# Wallboxsteuerung-WEMOS-ohne-shelly2.net
KiCad netlist of a schematic drawn in EAGLE
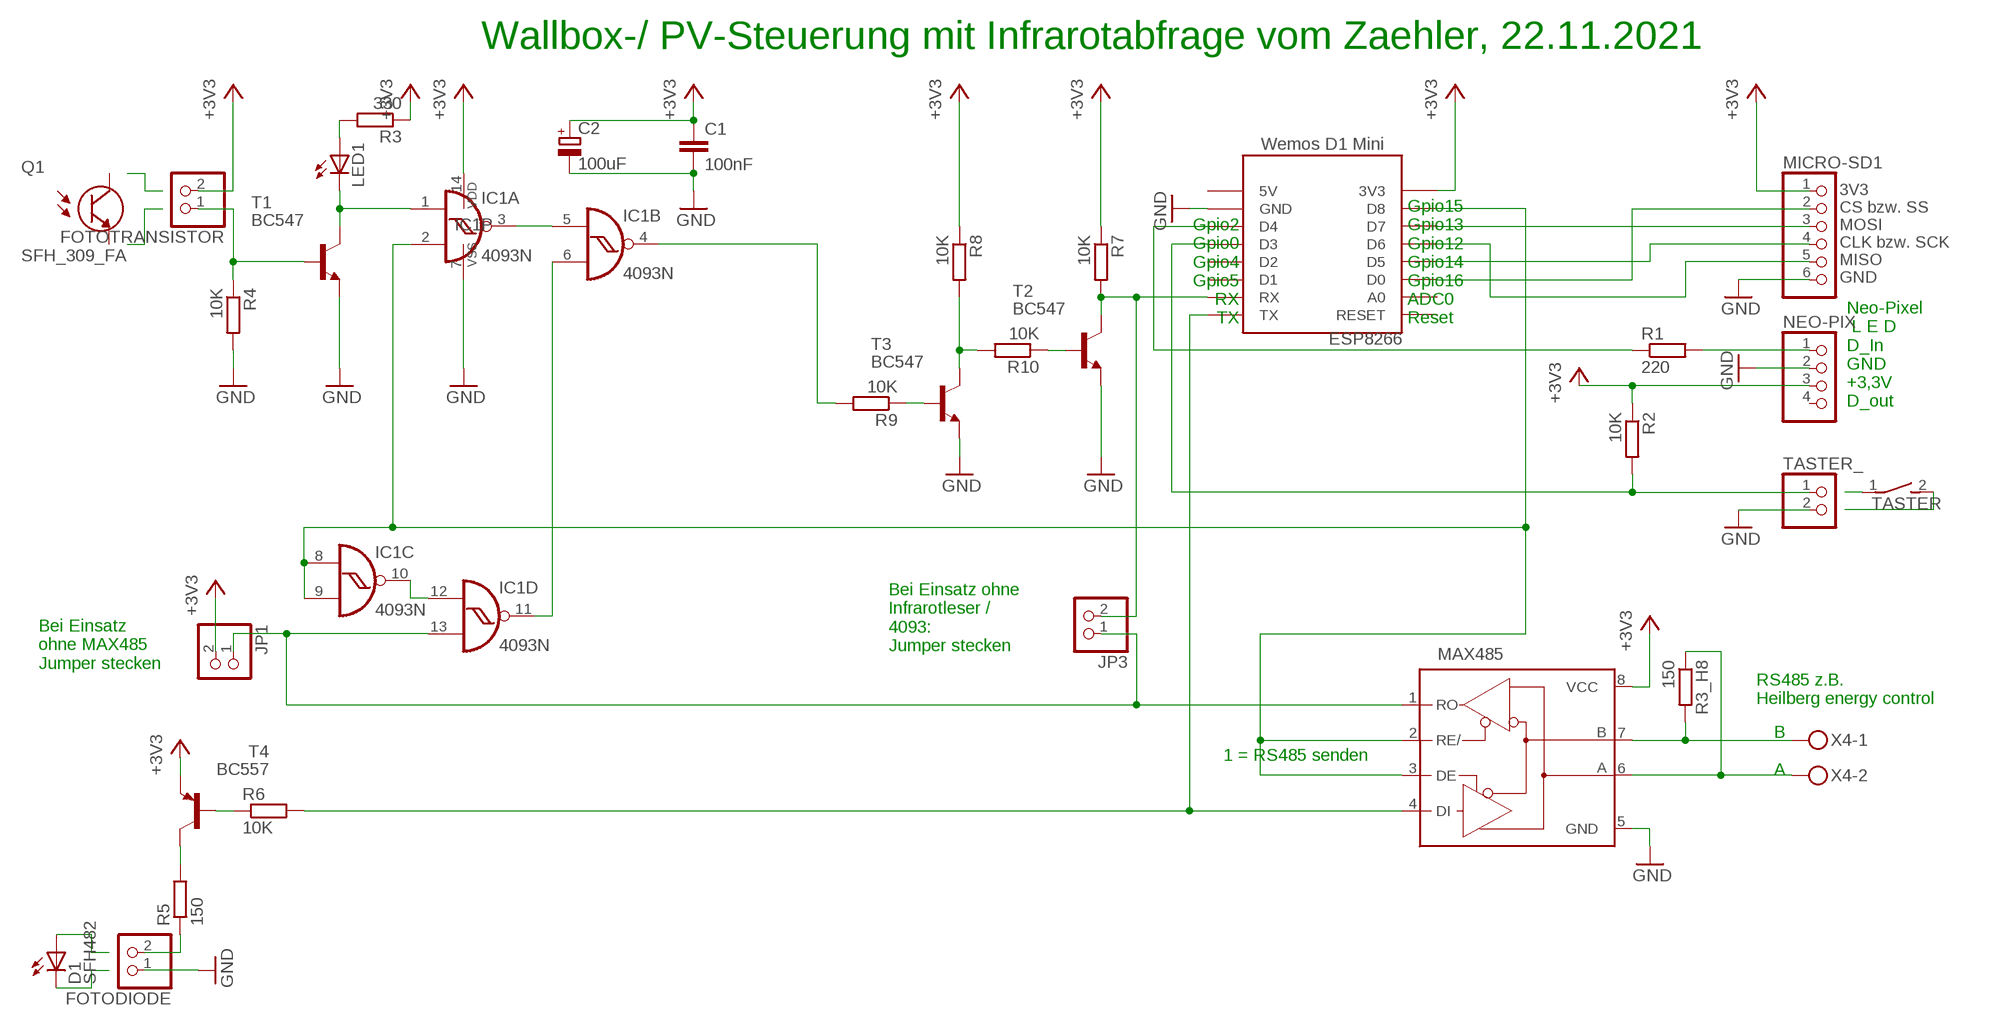
[diagram p0: schematic, sheet 1]

(export (version "E")
  (design (tool "Eeschema 10.0.6"))
  (components
    (comp (ref "C1")
      (value "100nF")
      (footprint "eagle-import:C050-045X075")
      (libsource (lib "eagle-import") (part "C-EU050-045X075"))
    )
    (comp (ref "C2")
      (value "100uF")
      (footprint "eagle-import:E5-6")
      (libsource (lib "eagle-import") (part "CPOL-EUE5-6"))
    )
    (comp (ref "D1")
      (value "SFH482")
      (footprint "eagle-import:SFH482")
      (libsource (lib "eagle-import") (part "SFH482"))
    )
    (comp (ref "ESP8266")
      (value "Wemos D1 Mini")
      (footprint "eagle-import:WEMOS-D1-MINI")
      (libsource (lib "eagle-import") (part "WEMOS-D1-MINI"))
    )
    (comp (ref "FOTODIODE")
      (value "PINHD-1X2")
      (footprint "eagle-import:1X02")
      (libsource (lib "eagle-import") (part "PINHD-1X2"))
    )
    (comp (ref "FOTOTRANSISTOR")
      (value "PINHD-1X2")
      (footprint "eagle-import:1X02")
      (libsource (lib "eagle-import") (part "PINHD-1X2"))
    )
    (comp (ref "IC1")
      (value "4093N")
      (footprint "eagle-import:DIL14")
      (libsource (lib "eagle-import") (part "4093N"))
    )
    (comp (ref "JP1")
      (value "PINHD-1X2")
      (footprint "eagle-import:1X02")
      (libsource (lib "eagle-import") (part "PINHD-1X2"))
    )
    (comp (ref "JP3")
      (value "PINHD-1X2")
      (footprint "eagle-import:1X02")
      (libsource (lib "eagle-import") (part "PINHD-1X2"))
    )
    (comp (ref "LED1")
      (value "LED5MM")
      (footprint "eagle-import:LED5MM")
      (libsource (lib "eagle-import") (part "LED5MM"))
    )
    (comp (ref "MAX485")
      (value "MAX3468CPA")
      (footprint "eagle-import:DIL08")
      (libsource (lib "eagle-import") (part "MAX34PA68C"))
    )
    (comp (ref "MICRO-SD1")
      (value "PINHD-1X6")
      (footprint "eagle-import:1X06")
      (libsource (lib "eagle-import") (part "PINHD-1X6"))
    )
    (comp (ref "NEO-PIX")
      (value "PINHD-1X4")
      (footprint "eagle-import:1X04")
      (libsource (lib "eagle-import") (part "PINHD-1X4"))
    )
    (comp (ref "Q1")
      (value "SFH_309_FA")
      (footprint "eagle-import:XDCR_SFH_309_FA")
      (fields (field (name "MANUFACTURER") "OSRAM"))
      (libsource (lib "eagle-import") (part "SFH_309_FA"))
    )
    (comp (ref "R1")
      (value "220")
      (footprint "eagle-import:0309V")
      (libsource (lib "eagle-import") (part "R-EU_0309/V"))
    )
    (comp (ref "R2")
      (value "10K")
      (footprint "eagle-import:0309V")
      (libsource (lib "eagle-import") (part "R-EU_0309/V"))
    )
    (comp (ref "R3")
      (value "330")
      (footprint "eagle-import:0309V")
      (libsource (lib "eagle-import") (part "R-EU_0309/V"))
    )
    (comp (ref "R3_H8")
      (value "150")
      (footprint "eagle-import:0309V")
      (libsource (lib "eagle-import") (part "R-EU_0309/V"))
    )
    (comp (ref "R4")
      (value "10K")
      (footprint "eagle-import:0309V")
      (libsource (lib "eagle-import") (part "R-EU_0309/V"))
    )
    (comp (ref "R5")
      (value "150")
      (footprint "eagle-import:0309V")
      (libsource (lib "eagle-import") (part "R-EU_0309/V"))
    )
    (comp (ref "R6")
      (value "10K")
      (footprint "eagle-import:0309V")
      (libsource (lib "eagle-import") (part "R-EU_0309/V"))
    )
    (comp (ref "R7")
      (value "10K")
      (footprint "eagle-import:0309V")
      (libsource (lib "eagle-import") (part "R-EU_0309/V"))
    )
    (comp (ref "R8")
      (value "10K")
      (footprint "eagle-import:0309V")
      (libsource (lib "eagle-import") (part "R-EU_0309/V"))
    )
    (comp (ref "R9")
      (value "10K")
      (footprint "eagle-import:0309V")
      (libsource (lib "eagle-import") (part "R-EU_0309/V"))
    )
    (comp (ref "R10")
      (value "10K")
      (footprint "eagle-import:0309V")
      (libsource (lib "eagle-import") (part "R-EU_0309/V"))
    )
    (comp (ref "T1")
      (value "BC547")
      (footprint "eagle-import:TO92")
      (libsource (lib "eagle-import") (part "BC547"))
    )
    (comp (ref "T2")
      (value "BC547")
      (footprint "eagle-import:TO92")
      (libsource (lib "eagle-import") (part "BC547"))
    )
    (comp (ref "T3")
      (value "BC547")
      (footprint "eagle-import:TO92")
      (libsource (lib "eagle-import") (part "BC547"))
    )
    (comp (ref "T4")
      (value "BC557")
      (footprint "eagle-import:TO92")
      (libsource (lib "eagle-import") (part "BC557"))
    )
    (comp (ref "TASTER")
      (value "DS01E")
      (footprint "eagle-import:DS-01")
      (libsource (lib "eagle-import") (part "DS01E"))
    )
    (comp (ref "TASTER_")
      (value "PINHD-1X2")
      (footprint "eagle-import:1X02")
      (libsource (lib "eagle-import") (part "PINHD-1X2"))
    )
    (comp (ref "X4")
      (value "MKDSN1,5/2-5,08")
      (footprint "eagle-import:MKDSN1,5_2-5,08")
      (libsource (lib "eagle-import") (part "MKDSN1,5/2-5,08"))
    )
  )
  (nets
    (net (code "1") (name "+3V3") (class "Default")
      (node (ref "C1") (pin "1") (pinfunction "1_1") (pintype "passive"))
      (node (ref "C2") (pin "+") (pinfunction "+_+") (pintype "passive"))
      (node (ref "ESP8266") (pin "3V3") (pinfunction "3V3_3V3") (pintype "bidirectional"))
      (node (ref "FOTOTRANSISTOR") (pin "2") (pinfunction "2_2") (pintype "passive"))
      (node (ref "IC1") (pin "14") (pinfunction "VDD_14") (pintype "power_in"))
      (node (ref "JP1") (pin "2") (pinfunction "2_2") (pintype "passive"))
      (node (ref "MAX485") (pin "8") (pinfunction "VCC_8") (pintype "power_in"))
      (node (ref "MICRO-SD1") (pin "1") (pinfunction "1_1") (pintype "passive"))
      (node (ref "NEO-PIX") (pin "3") (pinfunction "3_3") (pintype "passive"))
      (node (ref "R2") (pin "1") (pinfunction "1_1") (pintype "passive"))
      (node (ref "R3") (pin "1") (pinfunction "1_1") (pintype "passive"))
      (node (ref "R7") (pin "1") (pinfunction "1_1") (pintype "passive"))
      (node (ref "R8") (pin "1") (pinfunction "1_1") (pintype "passive"))
      (node (ref "T4") (pin "1") (pinfunction "E_1") (pintype "passive"))
    )
    (net (code "2") (name "GND") (class "Default")
      (node (ref "C1") (pin "2") (pinfunction "2_2") (pintype "passive"))
      (node (ref "C2") (pin "-") (pinfunction "-_-") (pintype "passive"))
      (node (ref "ESP8266") (pin "GND") (pinfunction "GND_GND") (pintype "bidirectional"))
      (node (ref "FOTODIODE") (pin "1") (pinfunction "1_1") (pintype "passive"))
      (node (ref "IC1") (pin "7") (pinfunction "VSS_7") (pintype "power_in"))
      (node (ref "MAX485") (pin "5") (pinfunction "GND_5") (pintype "power_in"))
      (node (ref "MICRO-SD1") (pin "6") (pinfunction "6_6") (pintype "passive"))
      (node (ref "NEO-PIX") (pin "2") (pinfunction "2_2") (pintype "passive"))
      (node (ref "R4") (pin "2") (pinfunction "2_2") (pintype "passive"))
      (node (ref "T1") (pin "1") (pinfunction "E_1") (pintype "passive"))
      (node (ref "T2") (pin "1") (pinfunction "E_1") (pintype "passive"))
      (node (ref "T3") (pin "1") (pinfunction "E_1") (pintype "passive"))
      (node (ref "TASTER_") (pin "2") (pinfunction "2_2") (pintype "passive"))
    )
    (net (code "3") (name "Net-(ESP8266-PadD0)") (class "Default")
      (node (ref "ESP8266") (pin "D0") (pinfunction "D0_D0") (pintype "bidirectional"))
      (node (ref "MICRO-SD1") (pin "2") (pinfunction "2_2") (pintype "passive"))
    )
    (net (code "4") (name "Net-(ESP8266-PadD3)") (class "Default")
      (node (ref "ESP8266") (pin "D3") (pinfunction "D3_D3") (pintype "bidirectional"))
      (node (ref "R2") (pin "2") (pinfunction "2_2") (pintype "passive"))
      (node (ref "TASTER_") (pin "1") (pinfunction "1_1") (pintype "passive"))
    )
    (net (code "5") (name "Net-(ESP8266-PadD4)") (class "Default")
      (node (ref "ESP8266") (pin "D4") (pinfunction "D4_D4") (pintype "bidirectional"))
      (node (ref "R1") (pin "1") (pinfunction "1_1") (pintype "passive"))
    )
    (net (code "6") (name "Net-(ESP8266-PadD5)") (class "Default")
      (node (ref "ESP8266") (pin "D5") (pinfunction "D5_D5") (pintype "bidirectional"))
      (node (ref "MICRO-SD1") (pin "4") (pinfunction "4_4") (pintype "passive"))
    )
    (net (code "7") (name "Net-(ESP8266-PadD6)") (class "Default")
      (node (ref "ESP8266") (pin "D6") (pinfunction "D6_D6") (pintype "bidirectional"))
      (node (ref "MICRO-SD1") (pin "5") (pinfunction "5_5") (pintype "passive"))
    )
    (net (code "8") (name "Net-(ESP8266-PadD7)") (class "Default")
      (node (ref "ESP8266") (pin "D7") (pinfunction "D7_D7") (pintype "bidirectional"))
      (node (ref "MICRO-SD1") (pin "3") (pinfunction "3_3") (pintype "passive"))
    )
    (net (code "9") (name "Net-(FOTODIODE-Pad2)") (class "Default")
      (node (ref "FOTODIODE") (pin "2") (pinfunction "2_2") (pintype "passive"))
      (node (ref "R5") (pin "1") (pinfunction "1_1") (pintype "passive"))
    )
    (net (code "10") (name "Net-(IC1A-I0)") (class "Default")
      (node (ref "IC1") (pin "1") (pinfunction "I0_1") (pintype "input"))
      (node (ref "LED1") (pin "K") (pinfunction "C_K") (pintype "passive"))
      (node (ref "T1") (pin "3") (pinfunction "C_3") (pintype "passive"))
    )
    (net (code "11") (name "Net-(IC1A-I1)") (class "Default")
      (node (ref "ESP8266") (pin "D8") (pinfunction "D8_D8") (pintype "bidirectional"))
      (node (ref "IC1") (pin "2") (pinfunction "I1_2") (pintype "input"))
      (node (ref "IC1") (pin "8") (pinfunction "I0_8") (pintype "input"))
      (node (ref "IC1") (pin "9") (pinfunction "I1_9") (pintype "input"))
      (node (ref "MAX485") (pin "2") (pinfunction "RE/_2") (pintype "input"))
      (node (ref "MAX485") (pin "3") (pinfunction "DE_3") (pintype "input"))
    )
    (net (code "12") (name "Net-(IC1A-O)") (class "Default")
      (node (ref "IC1") (pin "3") (pinfunction "O_3") (pintype "output"))
      (node (ref "IC1") (pin "5") (pinfunction "I0_5") (pintype "input"))
    )
    (net (code "13") (name "Net-(IC1B-I1)") (class "Default")
      (node (ref "IC1") (pin "11") (pinfunction "O_11") (pintype "output"))
      (node (ref "IC1") (pin "6") (pinfunction "I1_6") (pintype "input"))
    )
    (net (code "14") (name "Net-(IC1B-O)") (class "Default")
      (node (ref "IC1") (pin "4") (pinfunction "O_4") (pintype "output"))
      (node (ref "R9") (pin "2") (pinfunction "2_2") (pintype "passive"))
    )
    (net (code "15") (name "Net-(IC1C-O)") (class "Default")
      (node (ref "IC1") (pin "10") (pinfunction "O_10") (pintype "output"))
      (node (ref "IC1") (pin "12") (pinfunction "I0_12") (pintype "input"))
    )
    (net (code "16") (name "Net-(IC1D-I1)") (class "Default")
      (node (ref "IC1") (pin "13") (pinfunction "I1_13") (pintype "input"))
      (node (ref "JP1") (pin "1") (pinfunction "1_1") (pintype "passive"))
      (node (ref "JP3") (pin "1") (pinfunction "1_1") (pintype "passive"))
      (node (ref "MAX485") (pin "1") (pinfunction "RO_1") (pintype "output"))
    )
    (net (code "17") (name "Net-(LED1-PadA)") (class "Default")
      (node (ref "LED1") (pin "A") (pinfunction "A_A") (pintype "passive"))
      (node (ref "R3") (pin "2") (pinfunction "2_2") (pintype "passive"))
    )
    (net (code "18") (name "Net-(MAX485-A)") (class "Default")
      (node (ref "MAX485") (pin "6") (pinfunction "A_6") (pintype "passive"))
      (node (ref "R3_H8") (pin "1") (pinfunction "1_1") (pintype "passive"))
      (node (ref "X4") (pin "2") (pinfunction "KL_2") (pintype "passive"))
    )
    (net (code "19") (name "Net-(MAX485-B)") (class "Default")
      (node (ref "MAX485") (pin "7") (pinfunction "B_7") (pintype "passive"))
      (node (ref "R3_H8") (pin "2") (pinfunction "2_2") (pintype "passive"))
      (node (ref "X4") (pin "1") (pinfunction "KL_1") (pintype "passive"))
    )
    (net (code "20") (name "Net-(MAX485-DI)") (class "Default")
      (node (ref "ESP8266") (pin "TX") (pinfunction "TX_TX") (pintype "bidirectional"))
      (node (ref "MAX485") (pin "4") (pinfunction "DI_4") (pintype "input"))
      (node (ref "R6") (pin "2") (pinfunction "2_2") (pintype "passive"))
    )
    (net (code "21") (name "Net-(NEO-PIX-Pad1)") (class "Default")
      (node (ref "NEO-PIX") (pin "1") (pinfunction "1_1") (pintype "passive"))
      (node (ref "R1") (pin "2") (pinfunction "2_2") (pintype "passive"))
    )
    (net (code "22") (name "Net-(T1-B)") (class "Default")
      (node (ref "FOTOTRANSISTOR") (pin "1") (pinfunction "1_1") (pintype "passive"))
      (node (ref "R4") (pin "1") (pinfunction "1_1") (pintype "passive"))
      (node (ref "T1") (pin "2") (pinfunction "B_2") (pintype "passive"))
    )
    (net (code "23") (name "Net-(T2-B)") (class "Default")
      (node (ref "R10") (pin "1") (pinfunction "1_1") (pintype "passive"))
      (node (ref "T2") (pin "2") (pinfunction "B_2") (pintype "passive"))
    )
    (net (code "24") (name "Net-(T2-C)") (class "Default")
      (node (ref "ESP8266") (pin "RX") (pinfunction "RX_RX") (pintype "bidirectional"))
      (node (ref "JP3") (pin "2") (pinfunction "2_2") (pintype "passive"))
      (node (ref "R7") (pin "2") (pinfunction "2_2") (pintype "passive"))
      (node (ref "T2") (pin "3") (pinfunction "C_3") (pintype "passive"))
    )
    (net (code "25") (name "Net-(T3-B)") (class "Default")
      (node (ref "R9") (pin "1") (pinfunction "1_1") (pintype "passive"))
      (node (ref "T3") (pin "2") (pinfunction "B_2") (pintype "passive"))
    )
    (net (code "26") (name "Net-(T3-C)") (class "Default")
      (node (ref "R10") (pin "2") (pinfunction "2_2") (pintype "passive"))
      (node (ref "R8") (pin "2") (pinfunction "2_2") (pintype "passive"))
      (node (ref "T3") (pin "3") (pinfunction "C_3") (pintype "passive"))
    )
    (net (code "27") (name "Net-(T4-B)") (class "Default")
      (node (ref "R6") (pin "1") (pinfunction "1_1") (pintype "passive"))
      (node (ref "T4") (pin "2") (pinfunction "B_2") (pintype "passive"))
    )
    (net (code "28") (name "Net-(T4-C)") (class "Default")
      (node (ref "R5") (pin "2") (pinfunction "2_2") (pintype "passive"))
      (node (ref "T4") (pin "3") (pinfunction "C_3") (pintype "passive"))
    )
    (net (code "29") (name "unconnected-(D1-C-PadK)") (class "Default")
      (node (ref "D1") (pin "K") (pinfunction "C_K") (pintype "passive"))
    )
    (net (code "30") (name "unconnected-(D1-PadA)") (class "Default")
      (node (ref "D1") (pin "A") (pinfunction "A_A") (pintype "passive"))
    )
    (net (code "31") (name "unconnected-(ESP8266-Pad5V)") (class "Default")
      (node (ref "ESP8266") (pin "5V") (pinfunction "5V_5V") (pintype "bidirectional"))
    )
    (net (code "32") (name "unconnected-(ESP8266-PadA0)") (class "Default")
      (node (ref "ESP8266") (pin "A0") (pinfunction "A0_A0") (pintype "bidirectional"))
    )
    (net (code "33") (name "unconnected-(ESP8266-PadD1)") (class "Default")
      (node (ref "ESP8266") (pin "D1") (pinfunction "D1_D1") (pintype "bidirectional"))
    )
    (net (code "34") (name "unconnected-(ESP8266-PadD2)") (class "Default")
      (node (ref "ESP8266") (pin "D2") (pinfunction "D2_D2") (pintype "bidirectional"))
    )
    (net (code "35") (name "unconnected-(ESP8266-PadRESET)") (class "Default")
      (node (ref "ESP8266") (pin "RESET") (pinfunction "RESET_RESET") (pintype "bidirectional"))
    )
    (net (code "36") (name "unconnected-(NEO-PIX-Pad4)") (class "Default")
      (node (ref "NEO-PIX") (pin "4") (pinfunction "4_4") (pintype "passive"))
    )
    (net (code "37") (name "unconnected-(Q1-C-Pad2)") (class "Default")
      (node (ref "Q1") (pin "2") (pinfunction "C_2") (pintype "passive"))
    )
    (net (code "38") (name "unconnected-(Q1-E-Pad1)") (class "Default")
      (node (ref "Q1") (pin "1") (pinfunction "E_1") (pintype "passive"))
    )
    (net (code "39") (name "unconnected-(TASTER-Pad1)") (class "Default")
      (node (ref "TASTER") (pin "1") (pinfunction "1_1") (pintype "passive"))
    )
    (net (code "40") (name "unconnected-(TASTER-Pad2)") (class "Default")
      (node (ref "TASTER") (pin "2") (pinfunction "2_2") (pintype "passive"))
    )
  )
)
